# battery_pack.net
KiCad netlist of a schematic drawn in EAGLE
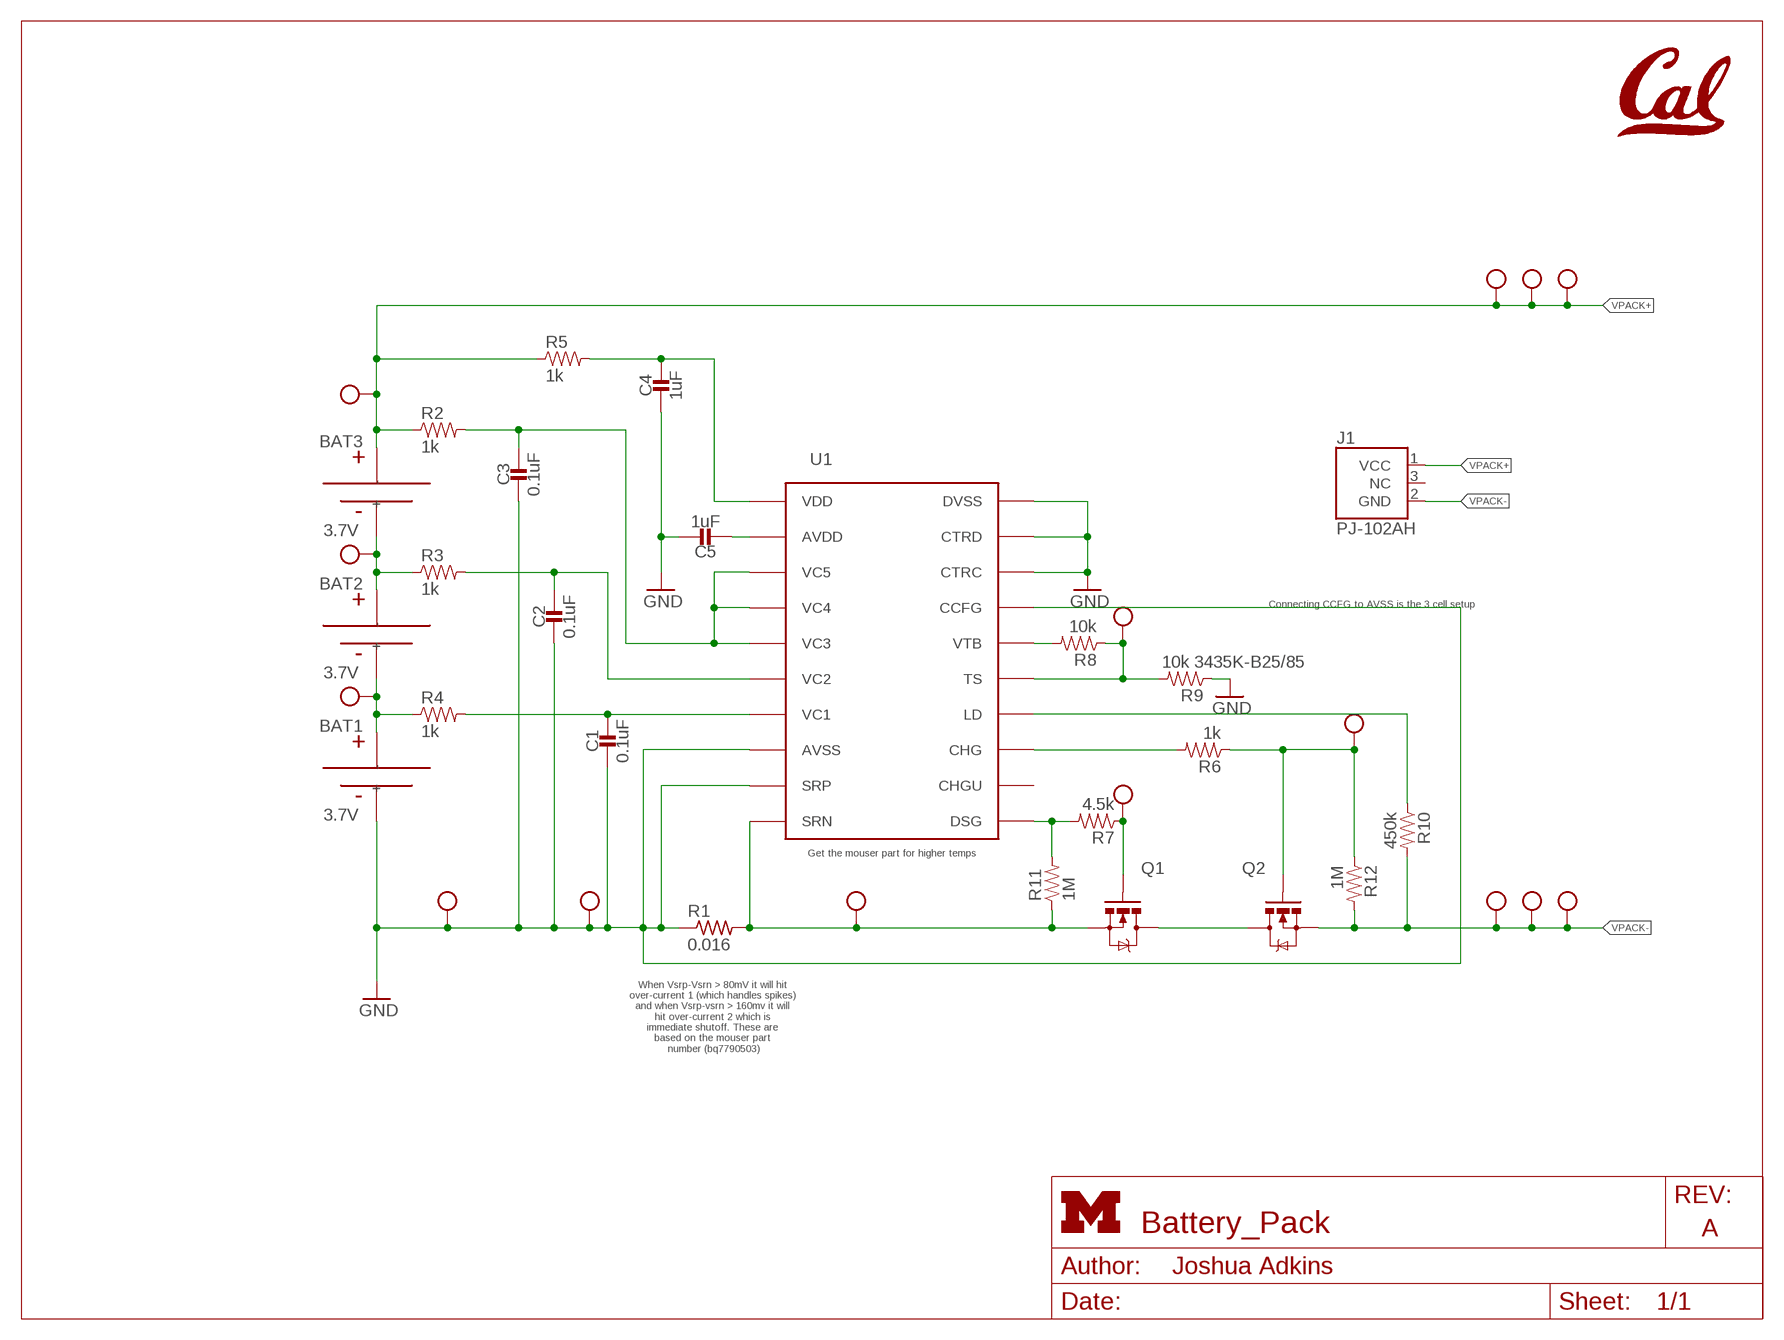
[diagram p0: schematic, sheet 1]

(export (version "E")
  (design (tool "Eeschema 10.0.6"))
  (components
    (comp (ref "BAT1")
      (value "3.7V")
      (footprint "eagle-import:PL-809797-1C")
      (libsource (lib "eagle-import") (part "BAT-CELL"))
    )
    (comp (ref "BAT2")
      (value "3.7V")
      (footprint "eagle-import:PL-809797-1C")
      (libsource (lib "eagle-import") (part "BAT-CELL"))
    )
    (comp (ref "BAT3")
      (value "3.7V")
      (footprint "eagle-import:PL-809797-1C")
      (libsource (lib "eagle-import") (part "BAT-CELL"))
    )
    (comp (ref "C1")
      (value "0.1uF")
      (footprint "eagle-import:0603_CAP")
      (libsource (lib "eagle-import") (part "CAPACITOR0603_CAP"))
    )
    (comp (ref "C2")
      (value "0.1uF")
      (footprint "eagle-import:0603_CAP")
      (libsource (lib "eagle-import") (part "CAPACITOR0603_CAP"))
    )
    (comp (ref "C3")
      (value "0.1uF")
      (footprint "eagle-import:0603_CAP")
      (libsource (lib "eagle-import") (part "CAPACITOR0603_CAP"))
    )
    (comp (ref "C4")
      (value "1uF")
      (footprint "eagle-import:0603_CAP")
      (libsource (lib "eagle-import") (part "CAPACITOR0603_CAP"))
    )
    (comp (ref "C5")
      (value "1uF")
      (footprint "eagle-import:0603_CAP")
      (libsource (lib "eagle-import") (part "CAPACITOR0603_CAP"))
    )
    (comp (ref "J1")
      (value "PJ-102AH")
      (footprint "eagle-import:PJ-102AH")
      (libsource (lib "eagle-import") (part "PJ-102AH"))
    )
    (comp (ref "Q1")
      (value "MOSFET-NCHANNELFDD8580")
      (footprint "eagle-import:DPAK")
      (libsource (lib "eagle-import") (part "MOSFET-NCHANNELFDD8580"))
    )
    (comp (ref "Q2")
      (value "MOSFET-NCHANNELFDD8580")
      (footprint "eagle-import:DPAK")
      (libsource (lib "eagle-import") (part "MOSFET-NCHANNELFDD8580"))
    )
    (comp (ref "R1")
      (value "0.016")
      (footprint "eagle-import:R1206")
      (libsource (lib "eagle-import") (part "R-US_R1206"))
    )
    (comp (ref "R2")
      (value "1k")
      (footprint "eagle-import:0603-RES")
      (libsource (lib "eagle-import") (part "RESISTOR0603_RES"))
    )
    (comp (ref "R3")
      (value "1k")
      (footprint "eagle-import:0603-RES")
      (libsource (lib "eagle-import") (part "RESISTOR0603_RES"))
    )
    (comp (ref "R4")
      (value "1k")
      (footprint "eagle-import:0603-RES")
      (libsource (lib "eagle-import") (part "RESISTOR0603_RES"))
    )
    (comp (ref "R5")
      (value "1k")
      (footprint "eagle-import:0603-RES")
      (libsource (lib "eagle-import") (part "RESISTOR0603_RES"))
    )
    (comp (ref "R6")
      (value "1k")
      (footprint "eagle-import:0603-RES")
      (libsource (lib "eagle-import") (part "RESISTOR0603_RES"))
    )
    (comp (ref "R7")
      (value "4.5k")
      (footprint "eagle-import:0603-RES")
      (libsource (lib "eagle-import") (part "RESISTOR0603_RES"))
    )
    (comp (ref "R8")
      (value "10k")
      (footprint "eagle-import:0603-RES")
      (libsource (lib "eagle-import") (part "RESISTOR0603_RES"))
    )
    (comp (ref "R9")
      (value "10k 3435K-B25/85")
      (footprint "eagle-import:0603-RES")
      (libsource (lib "eagle-import") (part "RESISTOR0603_RES"))
    )
    (comp (ref "R10")
      (value "450k")
      (footprint "eagle-import:0603-RES")
      (libsource (lib "eagle-import") (part "RESISTOR0603_RES"))
    )
    (comp (ref "R11")
      (value "1M")
      (footprint "eagle-import:0603-RES")
      (libsource (lib "eagle-import") (part "RESISTOR0603_RES"))
    )
    (comp (ref "R12")
      (value "1M")
      (footprint "eagle-import:0603-RES")
      (libsource (lib "eagle-import") (part "RESISTOR0603_RES"))
    )
    (comp (ref "TP1")
      (value "TEST_POINT_0.112IN")
      (footprint "eagle-import:TESTPOINT_0.112IN")
      (libsource (lib "eagle-import") (part "TEST_POINT_0.112IN"))
    )
    (comp (ref "TP2")
      (value "TEST_POINT_0.112IN")
      (footprint "eagle-import:TESTPOINT_0.112IN")
      (libsource (lib "eagle-import") (part "TEST_POINT_0.112IN"))
    )
    (comp (ref "TP3")
      (value "TEST_POINT_0.040IN")
      (footprint "eagle-import:TESTPOINT_0.040IN")
      (libsource (lib "eagle-import") (part "TEST_POINT_0.040IN"))
    )
    (comp (ref "TP4")
      (value "TEST_POINT_0.040IN")
      (footprint "eagle-import:TESTPOINT_0.040IN")
      (libsource (lib "eagle-import") (part "TEST_POINT_0.040IN"))
    )
    (comp (ref "TP5")
      (value "TEST_POINT_0.112IN")
      (footprint "eagle-import:TESTPOINT_0.112IN")
      (libsource (lib "eagle-import") (part "TEST_POINT_0.112IN"))
    )
    (comp (ref "TP6")
      (value "TEST_POINT_0.112IN")
      (footprint "eagle-import:TESTPOINT_0.112IN")
      (libsource (lib "eagle-import") (part "TEST_POINT_0.112IN"))
    )
    (comp (ref "TP7")
      (value "TEST_POINT_0.112IN")
      (footprint "eagle-import:TESTPOINT_0.112IN")
      (libsource (lib "eagle-import") (part "TEST_POINT_0.112IN"))
    )
    (comp (ref "TP8")
      (value "TEST_POINT_0.112IN")
      (footprint "eagle-import:TESTPOINT_0.112IN")
      (libsource (lib "eagle-import") (part "TEST_POINT_0.112IN"))
    )
    (comp (ref "TP9")
      (value "TEST_POINT_0.040IN")
      (footprint "eagle-import:TESTPOINT_0.040IN")
      (libsource (lib "eagle-import") (part "TEST_POINT_0.040IN"))
    )
    (comp (ref "TP10")
      (value "TEST_POINT_0.040IN")
      (footprint "eagle-import:TESTPOINT_0.040IN")
      (libsource (lib "eagle-import") (part "TEST_POINT_0.040IN"))
    )
    (comp (ref "TP11")
      (value "TEST_POINT_0.040IN")
      (footprint "eagle-import:TESTPOINT_0.040IN")
      (libsource (lib "eagle-import") (part "TEST_POINT_0.040IN"))
    )
    (comp (ref "TP12")
      (value "TEST_POINT_0.040IN")
      (footprint "eagle-import:TESTPOINT_0.040IN")
      (libsource (lib "eagle-import") (part "TEST_POINT_0.040IN"))
    )
    (comp (ref "TP13")
      (value "TEST_POINT_0.040IN")
      (footprint "eagle-import:TESTPOINT_0.040IN")
      (libsource (lib "eagle-import") (part "TEST_POINT_0.040IN"))
    )
    (comp (ref "TP14")
      (value "TEST_POINT_0.112IN")
      (footprint "eagle-import:TESTPOINT_0.112IN")
      (libsource (lib "eagle-import") (part "TEST_POINT_0.112IN"))
    )
    (comp (ref "TP15")
      (value "TEST_POINT_0.112IN")
      (footprint "eagle-import:TESTPOINT_0.112IN")
      (libsource (lib "eagle-import") (part "TEST_POINT_0.112IN"))
    )
    (comp (ref "U$1")
      (value "UCB_CAL500MIL")
      (footprint "eagle-import:UCB_CAL_500MIL")
      (libsource (lib "eagle-import") (part "UCB_CAL500MIL"))
    )
    (comp (ref "U1")
      (value "BQ77904")
      (footprint "eagle-import:TSSOP-20_6MM")
      (libsource (lib "eagle-import") (part "BQ77904"))
    )
  )
  (nets
    (net (code "1") (name "GND") (class "Default")
      (node (ref "BAT1") (pin "-") (pinfunction "-_-") (pintype "bidirectional"))
      (node (ref "C1") (pin "2") (pinfunction "2_2") (pintype "bidirectional"))
      (node (ref "C2") (pin "2") (pinfunction "2_2") (pintype "bidirectional"))
      (node (ref "C3") (pin "2") (pinfunction "2_2") (pintype "bidirectional"))
      (node (ref "C4") (pin "2") (pinfunction "2_2") (pintype "bidirectional"))
      (node (ref "C5") (pin "1") (pinfunction "1_1") (pintype "bidirectional"))
      (node (ref "R1") (pin "1") (pinfunction "1_1") (pintype "passive"))
      (node (ref "R9") (pin "1") (pinfunction "1_1") (pintype "passive"))
      (node (ref "TP7") (pin "1") (pinfunction "TESTPOINT_1") (pintype "bidirectional"))
      (node (ref "TP9") (pin "TESTPOINT") (pinfunction "TESTPOINT_TESTPOINT") (pintype "bidirectional"))
      (node (ref "U1") (pin "17") (pinfunction "CCFG_17") (pintype "bidirectional"))
      (node (ref "U1") (pin "18") (pinfunction "CTRC_18") (pintype "bidirectional"))
      (node (ref "U1") (pin "19") (pinfunction "CTRD_19") (pintype "bidirectional"))
      (node (ref "U1") (pin "20") (pinfunction "DVSS_20") (pintype "bidirectional"))
      (node (ref "U1") (pin "8") (pinfunction "AVSS_8") (pintype "bidirectional"))
      (node (ref "U1") (pin "9") (pinfunction "SRP_9") (pintype "bidirectional"))
    )
    (net (code "2") (name "Net-(Q1-D)") (class "Default")
      (node (ref "Q1") (pin "4") (pinfunction "D_4") (pintype "passive"))
      (node (ref "Q2") (pin "4") (pinfunction "D_4") (pintype "passive"))
    )
    (net (code "3") (name "Net-(Q1-G)") (class "Default")
      (node (ref "Q1") (pin "1") (pinfunction "G_1") (pintype "passive"))
      (node (ref "R7") (pin "1") (pinfunction "1_1") (pintype "passive"))
      (node (ref "TP11") (pin "TESTPOINT") (pinfunction "TESTPOINT_TESTPOINT") (pintype "bidirectional"))
    )
    (net (code "4") (name "Net-(Q1-S)") (class "Default")
      (node (ref "Q1") (pin "3") (pinfunction "S_3") (pintype "passive"))
      (node (ref "R1") (pin "2") (pinfunction "2_2") (pintype "passive"))
      (node (ref "R11") (pin "1") (pinfunction "1_1") (pintype "passive"))
      (node (ref "TP10") (pin "TESTPOINT") (pinfunction "TESTPOINT_TESTPOINT") (pintype "bidirectional"))
      (node (ref "U1") (pin "10") (pinfunction "SRN_10") (pintype "bidirectional"))
    )
    (net (code "5") (name "Net-(Q2-G)") (class "Default")
      (node (ref "Q2") (pin "1") (pinfunction "G_1") (pintype "passive"))
      (node (ref "R12") (pin "1") (pinfunction "1_1") (pintype "passive"))
      (node (ref "R6") (pin "1") (pinfunction "1_1") (pintype "passive"))
      (node (ref "TP12") (pin "TESTPOINT") (pinfunction "TESTPOINT_TESTPOINT") (pintype "bidirectional"))
    )
    (net (code "6") (name "Net-(TP14-TESTPOINT)") (class "Default")
      (node (ref "BAT2") (pin "+") (pinfunction "+_+") (pintype "bidirectional"))
      (node (ref "BAT3") (pin "-") (pinfunction "-_-") (pintype "bidirectional"))
      (node (ref "R3") (pin "1") (pinfunction "1_1") (pintype "passive"))
      (node (ref "TP14") (pin "1") (pinfunction "TESTPOINT_1") (pintype "bidirectional"))
    )
    (net (code "7") (name "Net-(TP15-TESTPOINT)") (class "Default")
      (node (ref "BAT1") (pin "+") (pinfunction "+_+") (pintype "bidirectional"))
      (node (ref "BAT2") (pin "-") (pinfunction "-_-") (pintype "bidirectional"))
      (node (ref "R4") (pin "1") (pinfunction "1_1") (pintype "passive"))
      (node (ref "TP15") (pin "1") (pinfunction "TESTPOINT_1") (pintype "bidirectional"))
    )
    (net (code "8") (name "Net-(U1-AVDD)") (class "Default")
      (node (ref "C5") (pin "2") (pinfunction "2_2") (pintype "bidirectional"))
      (node (ref "U1") (pin "2") (pinfunction "AVDD_2") (pintype "bidirectional"))
    )
    (net (code "9") (name "Net-(U1-CHG)") (class "Default")
      (node (ref "R6") (pin "2") (pinfunction "2_2") (pintype "passive"))
      (node (ref "U1") (pin "13") (pinfunction "CHG_13") (pintype "bidirectional"))
    )
    (net (code "10") (name "Net-(U1-DSG)") (class "Default")
      (node (ref "R11") (pin "2") (pinfunction "2_2") (pintype "passive"))
      (node (ref "R7") (pin "2") (pinfunction "2_2") (pintype "passive"))
      (node (ref "U1") (pin "11") (pinfunction "DSG_11") (pintype "bidirectional"))
    )
    (net (code "11") (name "Net-(U1-LD)") (class "Default")
      (node (ref "R10") (pin "1") (pinfunction "1_1") (pintype "passive"))
      (node (ref "U1") (pin "14") (pinfunction "LD_14") (pintype "bidirectional"))
    )
    (net (code "12") (name "Net-(U1-TS)") (class "Default")
      (node (ref "R8") (pin "1") (pinfunction "1_1") (pintype "passive"))
      (node (ref "R9") (pin "2") (pinfunction "2_2") (pintype "passive"))
      (node (ref "TP13") (pin "TESTPOINT") (pinfunction "TESTPOINT_TESTPOINT") (pintype "bidirectional"))
      (node (ref "U1") (pin "15") (pinfunction "TS_15") (pintype "bidirectional"))
    )
    (net (code "13") (name "Net-(U1-VC1)") (class "Default")
      (node (ref "C1") (pin "1") (pinfunction "1_1") (pintype "bidirectional"))
      (node (ref "R4") (pin "2") (pinfunction "2_2") (pintype "passive"))
      (node (ref "U1") (pin "7") (pinfunction "VC1_7") (pintype "bidirectional"))
    )
    (net (code "14") (name "Net-(U1-VC2)") (class "Default")
      (node (ref "C2") (pin "1") (pinfunction "1_1") (pintype "bidirectional"))
      (node (ref "R3") (pin "2") (pinfunction "2_2") (pintype "passive"))
      (node (ref "U1") (pin "6") (pinfunction "VC2_6") (pintype "bidirectional"))
    )
    (net (code "15") (name "Net-(U1-VC3)") (class "Default")
      (node (ref "C3") (pin "1") (pinfunction "1_1") (pintype "bidirectional"))
      (node (ref "R2") (pin "2") (pinfunction "2_2") (pintype "passive"))
      (node (ref "U1") (pin "3") (pinfunction "VC5_3") (pintype "bidirectional"))
      (node (ref "U1") (pin "4") (pinfunction "VC4_4") (pintype "bidirectional"))
      (node (ref "U1") (pin "5") (pinfunction "VC3_5") (pintype "bidirectional"))
    )
    (net (code "16") (name "Net-(U1-VDD)") (class "Default")
      (node (ref "C4") (pin "1") (pinfunction "1_1") (pintype "bidirectional"))
      (node (ref "R5") (pin "2") (pinfunction "2_2") (pintype "passive"))
      (node (ref "U1") (pin "1") (pinfunction "VDD_1") (pintype "bidirectional"))
    )
    (net (code "17") (name "Net-(U1-VTB)") (class "Default")
      (node (ref "R8") (pin "2") (pinfunction "2_2") (pintype "passive"))
      (node (ref "U1") (pin "16") (pinfunction "VTB_16") (pintype "bidirectional"))
    )
    (net (code "18") (name "VPACK+") (class "Default")
      (node (ref "BAT3") (pin "+") (pinfunction "+_+") (pintype "bidirectional"))
      (node (ref "J1") (pin "1") (pinfunction "VCC_1") (pintype "bidirectional"))
      (node (ref "R2") (pin "1") (pinfunction "1_1") (pintype "passive"))
      (node (ref "R5") (pin "1") (pinfunction "1_1") (pintype "passive"))
      (node (ref "TP1") (pin "1") (pinfunction "TESTPOINT_1") (pintype "bidirectional"))
      (node (ref "TP3") (pin "TESTPOINT") (pinfunction "TESTPOINT_TESTPOINT") (pintype "bidirectional"))
      (node (ref "TP6") (pin "1") (pinfunction "TESTPOINT_1") (pintype "bidirectional"))
      (node (ref "TP8") (pin "1") (pinfunction "TESTPOINT_1") (pintype "bidirectional"))
    )
    (net (code "19") (name "VPACK-") (class "Default")
      (node (ref "J1") (pin "2") (pinfunction "GND_2") (pintype "bidirectional"))
      (node (ref "Q2") (pin "3") (pinfunction "S_3") (pintype "passive"))
      (node (ref "R10") (pin "2") (pinfunction "2_2") (pintype "passive"))
      (node (ref "R12") (pin "2") (pinfunction "2_2") (pintype "passive"))
      (node (ref "TP2") (pin "1") (pinfunction "TESTPOINT_1") (pintype "bidirectional"))
      (node (ref "TP4") (pin "TESTPOINT") (pinfunction "TESTPOINT_TESTPOINT") (pintype "bidirectional"))
      (node (ref "TP5") (pin "1") (pinfunction "TESTPOINT_1") (pintype "bidirectional"))
    )
    (net (code "20") (name "unconnected-(J1-NC-Pad3)") (class "Default")
      (node (ref "J1") (pin "3") (pinfunction "NC_3") (pintype "bidirectional"))
    )
    (net (code "21") (name "unconnected-(U1-CHGU-Pad12)") (class "Default")
      (node (ref "U1") (pin "12") (pinfunction "CHGU_12") (pintype "bidirectional"))
    )
  )
)
